# analog.net
KiCad netlist of a schematic drawn in Altium Designer
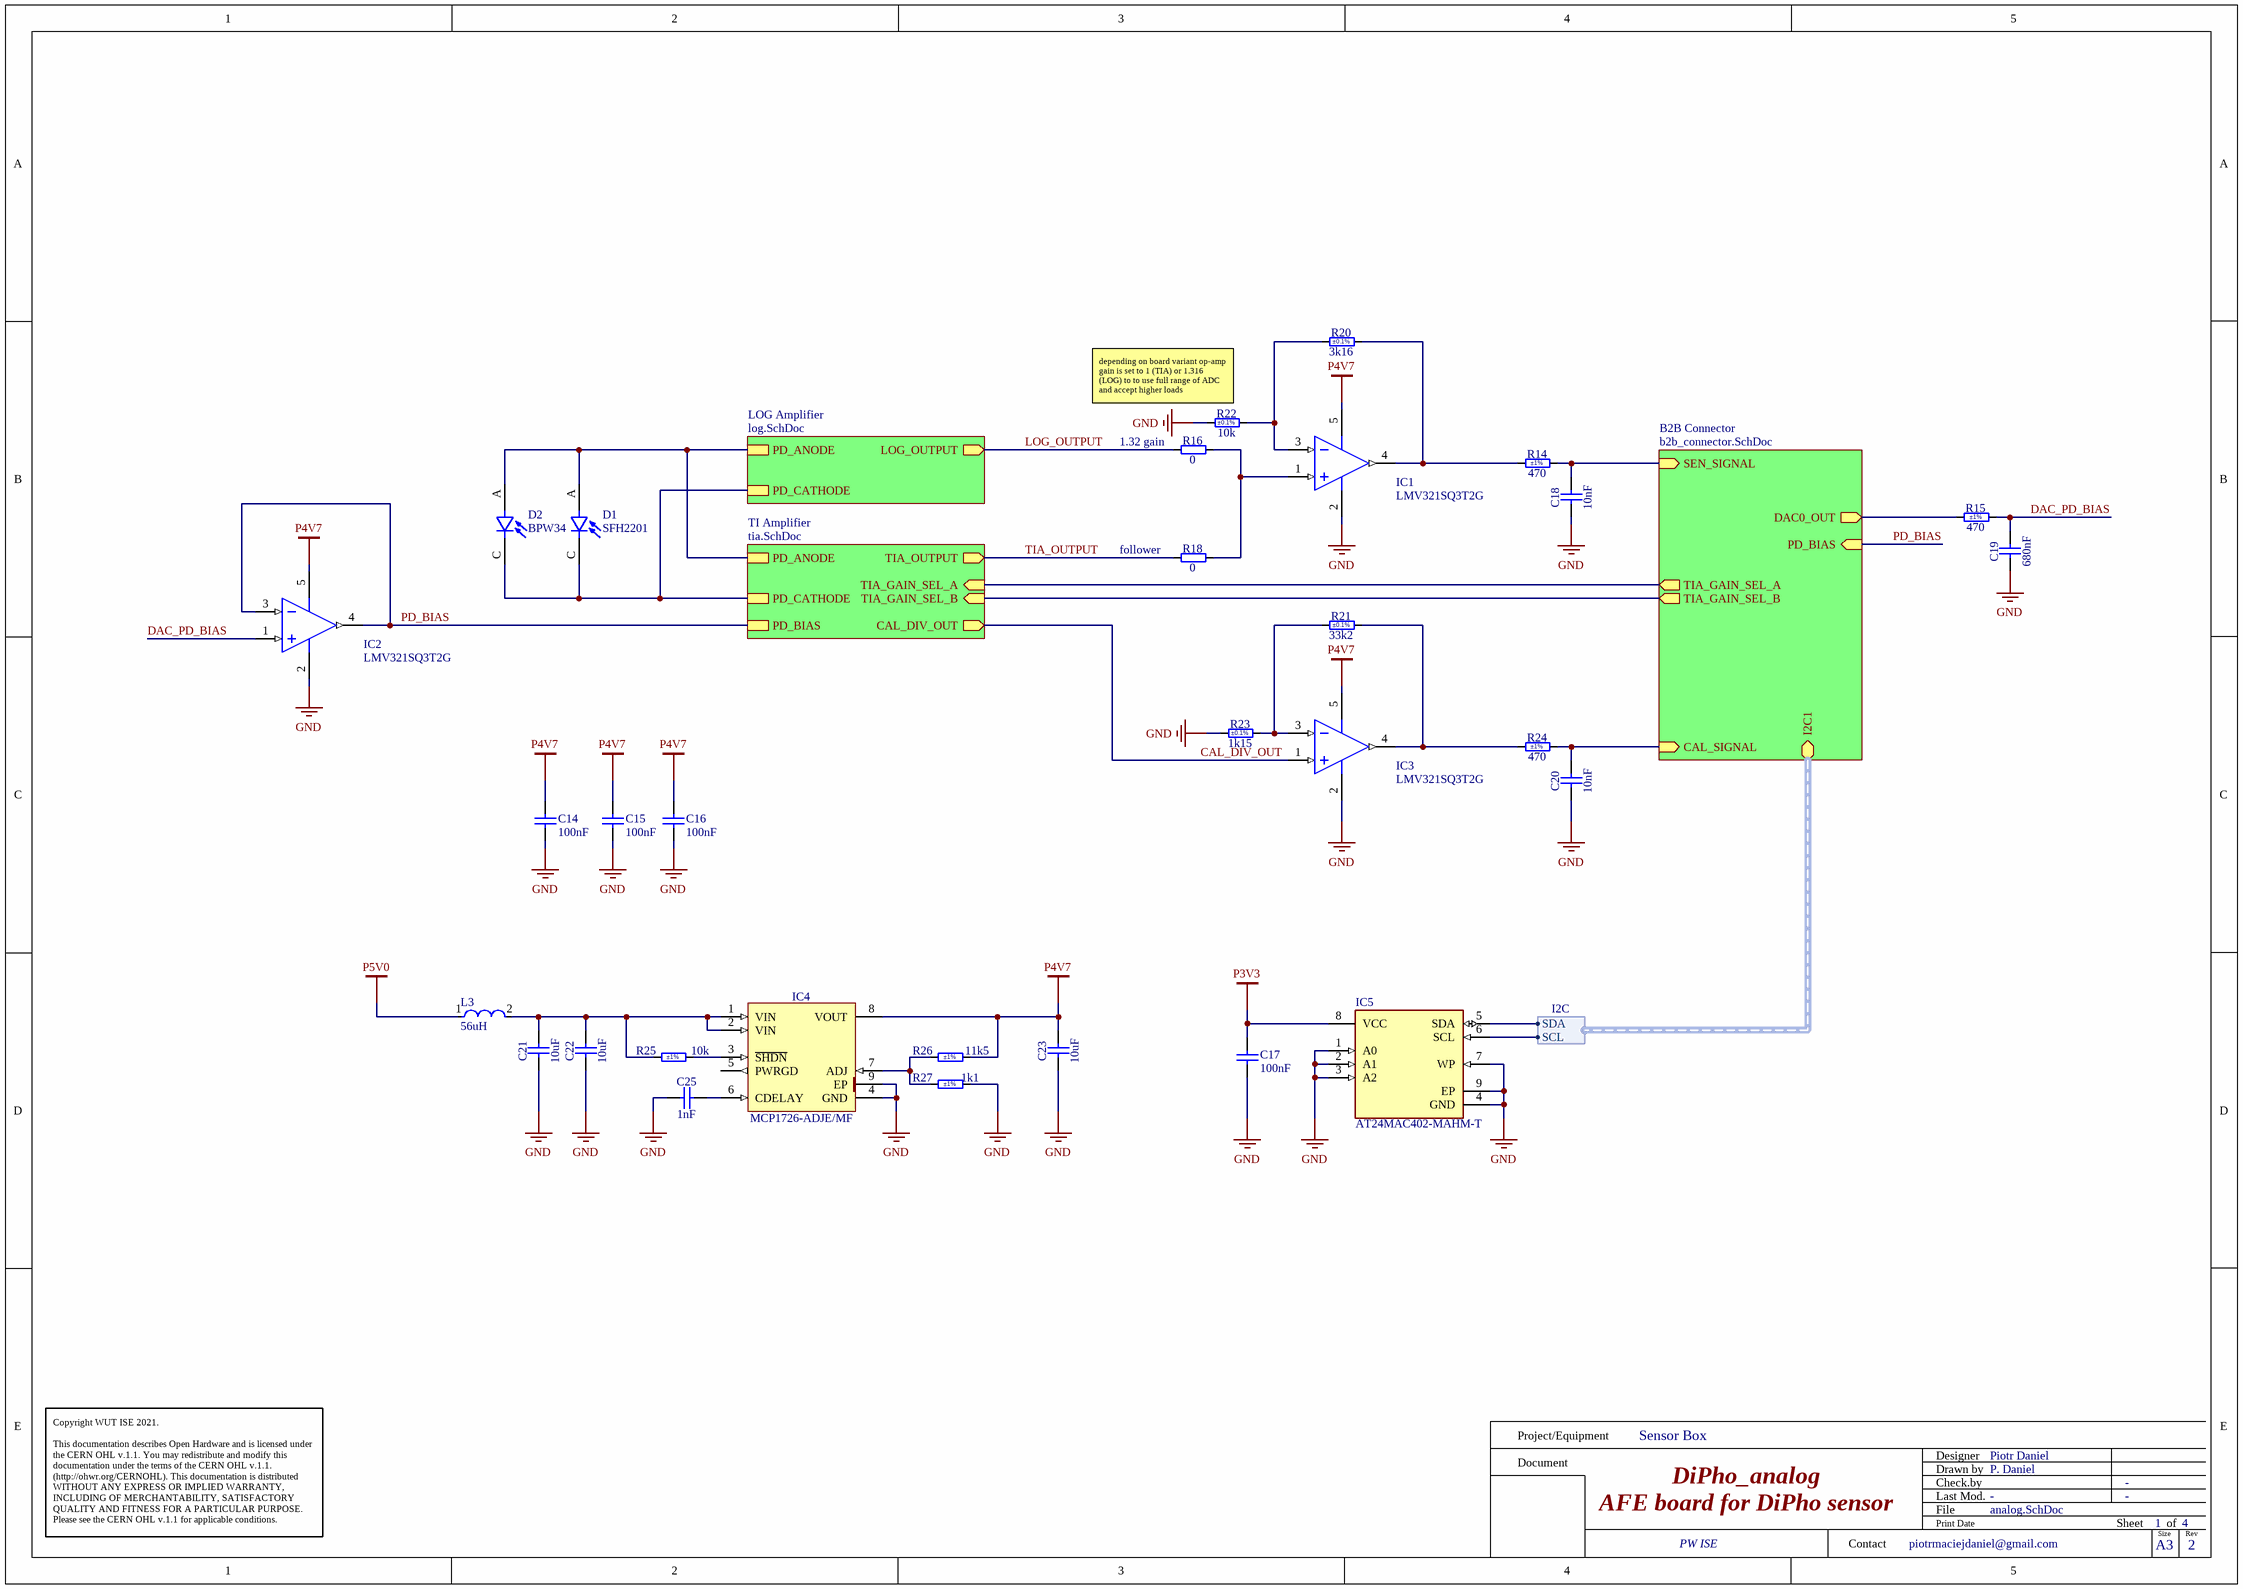
[diagram p0: analog.SchDoc]

(export (version "E")
  (design (tool "Eeschema 10.0.6"))
  (components
    (comp (ref "C14")
      (value "100nF")
      (footprint "CAPC1005X55N")
      (description "Non-polarised capacitor")
      (fields
        (field (name "TOLERANCE") "±10%")
        (field (name "VOLTAGE") "16V")
        (field (name "AUTHOR") "CERN DEM JLC")
      )
      (libsource (lib "Capacitors") (part "Capacitor - non polarized"))
    )
    (comp (ref "C15")
      (value "100nF")
      (footprint "CAPC1005X55N")
      (description "Non-polarised capacitor")
      (fields
        (field (name "TOLERANCE") "±10%")
        (field (name "VOLTAGE") "16V")
        (field (name "AUTHOR") "CERN DEM JLC")
      )
      (libsource (lib "Capacitors") (part "Capacitor - non polarized"))
    )
    (comp (ref "C16")
      (value "100nF")
      (footprint "CAPC1005X55N")
      (description "Non-polarised capacitor")
      (fields
        (field (name "TOLERANCE") "±10%")
        (field (name "VOLTAGE") "16V")
        (field (name "AUTHOR") "CERN DEM JLC")
      )
      (libsource (lib "Capacitors") (part "Capacitor - non polarized"))
    )
    (comp (ref "C17")
      (value "100nF")
      (footprint "CAPC1005X55N")
      (description "Non-polarised capacitor")
      (fields
        (field (name "TOLERANCE") "±10%")
        (field (name "VOLTAGE") "16V")
        (field (name "AUTHOR") "CERN DEM JLC")
      )
      (libsource (lib "Capacitors") (part "Capacitor - non polarized"))
    )
    (comp (ref "C18")
      (value "10nF")
      (footprint "CAPC1005X55N")
      (description "Non-polarised capacitor")
      (fields
        (field (name "PART NUMBER") "CC0402_10NF_16V_10%_X7R")
        (field (name "VOLTAGE") "16V")
        (field (name "AUTHOR") "CERN DEM JLC")
      )
      (libsource (lib "Capacitors") (part "Capacitor - non polarized"))
    )
    (comp (ref "C19")
      (value "680nF")
      (footprint "CAPC1005X55N")
      (description "Non-polarised capacitor")
      (fields
        (field (name "PART NUMBER") "CC0402_680NF_10V_10%_X5R")
        (field (name "VOLTAGE") "10V")
        (field (name "AUTHOR") "CERN DEM BC")
      )
      (libsource (lib "Capacitors") (part "Capacitor - non polarized"))
    )
    (comp (ref "C20")
      (value "10nF")
      (footprint "CAPC1005X55N")
      (description "Non-polarised capacitor")
      (fields
        (field (name "PART NUMBER") "CC0402_10NF_16V_10%_X7R")
        (field (name "VOLTAGE") "16V")
        (field (name "AUTHOR") "CERN DEM JLC")
      )
      (libsource (lib "Capacitors") (part "Capacitor - non polarized"))
    )
    (comp (ref "C21")
      (value "10uF")
      (footprint "CAPC2012X135N")
      (description "Non-polarised capacitor")
      (fields
        (field (name "PART NUMBER") "CC0805_10UF_10V_10%_X7R")
        (field (name "VOLTAGE") "10V")
        (field (name "AUTHOR") "CERN DEM JLC")
      )
      (libsource (lib "Capacitors") (part "Capacitor - non polarized"))
    )
    (comp (ref "C22")
      (value "10uF")
      (footprint "CAPC2012X135N")
      (description "Non-polarised capacitor")
      (fields
        (field (name "PART NUMBER") "CC0805_10UF_10V_10%_X7R")
        (field (name "VOLTAGE") "10V")
        (field (name "AUTHOR") "CERN DEM JLC")
      )
      (libsource (lib "Capacitors") (part "Capacitor - non polarized"))
    )
    (comp (ref "C23")
      (value "10uF")
      (footprint "CAPC2012X135N")
      (description "Non-polarised capacitor")
      (fields
        (field (name "PART NUMBER") "CC0805_10UF_10V_10%_X7R")
        (field (name "VOLTAGE") "10V")
        (field (name "AUTHOR") "CERN DEM JLC")
      )
      (libsource (lib "Capacitors") (part "Capacitor - non polarized"))
    )
    (comp (ref "C25")
      (value "1nF")
      (footprint "CAPC1005X55N")
      (description "Non-polarised capacitor")
      (fields
        (field (name "PART NUMBER") "CC0402_1NF_50V_10%_X7R")
        (field (name "VOLTAGE") "50V")
        (field (name "AUTHOR") "CERN DEM JLC")
      )
      (libsource (lib "Capacitors") (part "Capacitor - non polarized"))
    )
    (comp (ref "D1") (value "SFH2201") (footprint "SFH_2201") (libsource (lib "DiPho") (part "SFH2201")))
    (comp (ref "D2")
      (value "BPW34")
      (footprint "BPW34")
      (description "VISHAY - BPW34 - Photodiode, 65 °, 2 nA, 900 nm, DIP-2")
      (fields (field (name "MANUFACTURER") "Vishay"))
      (libsource (lib "DiPho") (part "BPW34"))
    )
    (comp (ref "IC1")
      (value "LMV321SQ3T2G")
      (footprint "ONSC-SC70-5-419A-02_K_N")
      (fields (field (name "MANUFACTURER") "On Semiconductor"))
      (libsource (lib "Altium Content Vault") (part "ONSC-LMV321-SC70-5-419A-02"))
    )
    (comp (ref "IC2")
      (value "LMV321SQ3T2G")
      (footprint "ONSC-SC70-5-419A-02_K_N")
      (fields (field (name "MANUFACTURER") "On Semiconductor"))
      (libsource (lib "Altium Content Vault") (part "ONSC-LMV321-SC70-5-419A-02"))
    )
    (comp (ref "IC3")
      (value "LMV321SQ3T2G")
      (footprint "ONSC-SC70-5-419A-02_K_N")
      (fields (field (name "MANUFACTURER") "On Semiconductor"))
      (libsource (lib "Altium Content Vault") (part "ONSC-LMV321-SC70-5-419A-02"))
    )
    (comp (ref "IC4")
      (value "MCP1726-ADJE/MF")
      (footprint "SON65P300X300X100-9N-R160X240")
      (description "1A, 0.8V to 5.0V Adjustable , Low Quiescent Current LDO Regulator")
      (fields (field (name "MANUFACTURER") "MICROCHIP TECHNOLOGY") (field (name "AUTHOR") "CERN DEM JLC"))
      (libsource (lib "ICs And Semiconductors") (part "MCP1726-ADJE/MF"))
    )
    (comp (ref "IC5")
      (value "AT24MAC402-MAHM-T")
      (footprint "FP-C04-21355-Q4B-MFG")
      (description "IC EEPROM 2K I2C 1MHZ 8UDFN")
      (libsource (lib "Altium Content Vault") (part "d3f380e7e9881dc7528c8402481fd2f"))
    )
    (comp (ref "L3")
      (value "56uH")
      (footprint "FP-LQH3NPH_ME-MFG")
      (description "Wire Wound Ferrite Inductor for Power Lines 56μH ±20% 1.2Ω 500mA 1212")
      (libsource (lib "Altium Content Vault") (part "725321dda6339637d4d059423bc1c3c"))
    )
    (comp (ref "R14")
      (value "470")
      (footprint "RESC1005X40N")
      (description "Resistor - 1%")
      (fields
        (field (name "TOLERANCE") "±1%")
        (field (name "PART NUMBER") "R0402_470R_1%_0.0625W_100PPM")
        (field (name "POWER") "0.0625W")
        (field (name "AUTHOR") "CERN DEM JLC")
      )
      (libsource (lib "Resistors") (part "Resistor - 1%"))
    )
    (comp (ref "R15")
      (value "470")
      (footprint "RESC1005X40N")
      (description "Resistor - 1%")
      (fields
        (field (name "TOLERANCE") "±1%")
        (field (name "PART NUMBER") "R0402_470R_1%_0.0625W_100PPM")
        (field (name "POWER") "0.0625W")
        (field (name "AUTHOR") "CERN DEM JLC")
      )
      (libsource (lib "Resistors") (part "Resistor - 1%"))
    )
    (comp (ref "R16")
      (value "0")
      (footprint "RESC1005X40N")
      (description "Resistor")
      (fields
        (field (name "PART NUMBER") "R0402_0R_JUMPER")
        (field (name "MANUFACTURER") "GENERIC")
        (field (name "AUTHOR") "CERN DEM JLC")
      )
      (libsource (lib "Resistors") (part "Resistor"))
    )
    (comp (ref "R18")
      (value "0")
      (footprint "RESC1005X40N")
      (description "Resistor")
      (fields
        (field (name "PART NUMBER") "R0402_0R_JUMPER")
        (field (name "MANUFACTURER") "GENERIC")
        (field (name "AUTHOR") "CERN DEM JLC")
      )
      (libsource (lib "Resistors") (part "Resistor"))
    )
    (comp (ref "R20")
      (value "3k16")
      (footprint "RESC1005X35N")
      (description "Resistor - 0.1%")
      (fields
        (field (name "TOLERANCE") "±0.1%")
        (field (name "PART NUMBER") "R0402_10K_0.1%_0.063W_25PPM")
        (field (name "POWER") "0.063W")
        (field (name "AUTHOR") "CERN DEM JMW")
      )
      (libsource (lib "Resistors") (part "Resistor - 0.1%"))
    )
    (comp (ref "R21")
      (value "33k2")
      (footprint "RESC1005X40N")
      (description "Resistor - 0.1%")
      (fields
        (field (name "TOLERANCE") "±0.1%")
        (field (name "PART NUMBER") "R0402_33K2_0.1%_0.063W_25PPM")
        (field (name "POWER") "0.063W")
        (field (name "AUTHOR") "CERN DEM BC")
      )
      (libsource (lib "Resistors") (part "Resistor - 0.1%"))
    )
    (comp (ref "R22")
      (value "10k")
      (footprint "RESC1005X35N")
      (description "Resistor - 0.1%")
      (fields
        (field (name "TOLERANCE") "±0.1%")
        (field (name "PART NUMBER") "R0402_10K_0.1%_0.063W_25PPM")
        (field (name "POWER") "0.063W")
        (field (name "AUTHOR") "CERN DEM JMW")
      )
      (libsource (lib "Resistors") (part "Resistor - 0.1%"))
    )
    (comp (ref "R23")
      (value "1k15")
      (footprint "RESC1005X35N")
      (description "Resistor - 0.1%")
      (fields
        (field (name "TOLERANCE") "±0.1%")
        (field (name "PART NUMBER") "R0402_10K_0.1%_0.063W_25PPM")
        (field (name "POWER") "0.063W")
        (field (name "AUTHOR") "CERN DEM JMW")
      )
      (libsource (lib "Resistors") (part "Resistor - 0.1%"))
    )
    (comp (ref "R24")
      (value "470")
      (footprint "RESC1005X40N")
      (description "Resistor - 1%")
      (fields
        (field (name "TOLERANCE") "±1%")
        (field (name "PART NUMBER") "R0402_470R_1%_0.0625W_100PPM")
        (field (name "POWER") "0.0625W")
        (field (name "AUTHOR") "CERN DEM JLC")
      )
      (libsource (lib "Resistors") (part "Resistor - 1%"))
    )
    (comp (ref "R25")
      (value "10k")
      (footprint "RESC1005X40N")
      (description "Resistor - 1%")
      (fields
        (field (name "TOLERANCE") "±1%")
        (field (name "PART NUMBER") "R0402_10K_1%_0.0625W_100PPM")
        (field (name "POWER") "0.0625W")
        (field (name "AUTHOR") "CERN DEM JLC")
      )
      (libsource (lib "Resistors") (part "Resistor - 1%"))
    )
    (comp (ref "R26")
      (value "11k5")
      (footprint "RESC1005X40N")
      (description "Resistor - 1%")
      (fields
        (field (name "TOLERANCE") "±1%")
        (field (name "PART NUMBER") "R0402_11K5_1%_0.063W_100PPM")
        (field (name "POWER") "0.063W")
        (field (name "AUTHOR") "CERN DEM BC")
      )
      (libsource (lib "Resistors") (part "Resistor - 1%"))
    )
    (comp (ref "R27")
      (value "1k1")
      (footprint "RESC1005X40N")
      (description "Resistor - 1%")
      (fields
        (field (name "TOLERANCE") "±1%")
        (field (name "PART NUMBER") "R0402_1K1_1%_0.0625W_100PPM")
        (field (name "POWER") "0.0625W")
        (field (name "AUTHOR") "CERN DEM JLC")
      )
      (libsource (lib "Resistors") (part "Resistor - 1%"))
    )
  )
  (nets
    (net (code "2") (name "/CAL_DIV_OUT") (class "Default")
      (node (ref "IC3") (pin "1") (pinfunction "IN+_1") (pintype "input"))
    )
    (net (code "3") (name "/CAL_SIGNAL") (class "Default")
      (node (ref "C20") (pin "2") (pinfunction "2_2") (pintype "passive"))
      (node (ref "R24") (pin "2") (pinfunction "2_2") (pintype "passive"))
    )
    (net (code "4") (name "/DAC0_OUT") (class "Default")
      (node (ref "R15") (pin "1") (pinfunction "1_1") (pintype "passive"))
    )
    (net (code "5") (name "/DAC_PD_BIAS") (class "Default")
      (node (ref "C19") (pin "2") (pinfunction "2_2") (pintype "passive"))
      (node (ref "IC2") (pin "1") (pinfunction "IN+_1") (pintype "input"))
      (node (ref "R15") (pin "2") (pinfunction "2_2") (pintype "passive"))
    )
    (net (code "6") (name "/LOG_OUTPUT") (class "Default")
      (node (ref "R16") (pin "1") (pinfunction "1_1") (pintype "passive"))
    )
    (net (code "7") (name "/PD_ANODE") (class "Default")
      (node (ref "D1") (pin "A") (pinfunction "A_A") (pintype "passive"))
      (node (ref "D2") (pin "A") (pinfunction "A_A") (pintype "passive"))
    )
    (net (code "8") (name "/PD_BIAS") (class "Default")
      (node (ref "IC2") (pin "3") (pinfunction "IN-_3") (pintype "input"))
      (node (ref "IC2") (pin "4") (pinfunction "OUT_4") (pintype "output"))
    )
    (net (code "9") (name "/PD_CATHODE") (class "Default")
      (node (ref "D1") (pin "C") (pinfunction "C_C") (pintype "passive"))
      (node (ref "D2") (pin "C") (pinfunction "C_C") (pintype "passive"))
    )
    (net (code "10") (name "/SCL") (class "Default")
      (node (ref "IC5") (pin "6") (pinfunction "SCL_6") (pintype "input"))
    )
    (net (code "11") (name "/SDA") (class "Default")
      (node (ref "IC5") (pin "5") (pinfunction "SDA_5") (pintype "bidirectional"))
    )
    (net (code "12") (name "/SEN_SIGNAL") (class "Default")
      (node (ref "C18") (pin "2") (pinfunction "2_2") (pintype "passive"))
      (node (ref "R14") (pin "2") (pinfunction "2_2") (pintype "passive"))
    )
    (net (code "15") (name "/TIA_OUTPUT") (class "Default")
      (node (ref "R18") (pin "1") (pinfunction "1_1") (pintype "passive"))
    )
    (net (code "17") (name "GND") (class "Default")
      (node (ref "C14") (pin "1") (pinfunction "1_1") (pintype "passive"))
      (node (ref "C15") (pin "1") (pinfunction "1_1") (pintype "passive"))
      (node (ref "C16") (pin "1") (pinfunction "1_1") (pintype "passive"))
      (node (ref "C17") (pin "1") (pinfunction "1_1") (pintype "passive"))
      (node (ref "C18") (pin "1") (pinfunction "1_1") (pintype "passive"))
      (node (ref "C19") (pin "1") (pinfunction "1_1") (pintype "passive"))
      (node (ref "C20") (pin "1") (pinfunction "1_1") (pintype "passive"))
      (node (ref "C21") (pin "1") (pinfunction "1_1") (pintype "passive"))
      (node (ref "C22") (pin "1") (pinfunction "1_1") (pintype "passive"))
      (node (ref "C23") (pin "1") (pinfunction "1_1") (pintype "passive"))
      (node (ref "C25") (pin "1") (pinfunction "1_1") (pintype "passive"))
      (node (ref "IC1") (pin "2") (pinfunction "V-_2") (pintype "power_in"))
      (node (ref "IC2") (pin "2") (pinfunction "V-_2") (pintype "power_in"))
      (node (ref "IC3") (pin "2") (pinfunction "V-_2") (pintype "power_in"))
      (node (ref "IC4") (pin "4") (pinfunction "GND_4") (pintype "power_in"))
      (node (ref "IC4") (pin "9") (pinfunction "EP_9") (pintype "power_in"))
      (node (ref "IC5") (pin "1") (pinfunction "A0_1") (pintype "input"))
      (node (ref "IC5") (pin "2") (pinfunction "A1_2") (pintype "input"))
      (node (ref "IC5") (pin "3") (pinfunction "A2_3") (pintype "input"))
      (node (ref "IC5") (pin "4") (pinfunction "GND_4") (pintype "power_in"))
      (node (ref "IC5") (pin "7") (pinfunction "WP_7") (pintype "input"))
      (node (ref "IC5") (pin "9") (pinfunction "EP_9") (pintype "power_in"))
      (node (ref "R22") (pin "1") (pinfunction "1_1") (pintype "passive"))
      (node (ref "R23") (pin "1") (pinfunction "1_1") (pintype "passive"))
      (node (ref "R27") (pin "2") (pinfunction "2_2") (pintype "passive"))
    )
    (net (code "18") (name "Net-(C21-Pad2)") (class "Default")
      (node (ref "C21") (pin "2") (pinfunction "2_2") (pintype "passive"))
      (node (ref "C22") (pin "2") (pinfunction "2_2") (pintype "passive"))
      (node (ref "IC4") (pin "1") (pinfunction "VIN_1") (pintype "input"))
      (node (ref "IC4") (pin "2") (pinfunction "VIN_2") (pintype "input"))
      (node (ref "L3") (pin "2") (pinfunction "2_2") (pintype "passive"))
      (node (ref "R25") (pin "1") (pinfunction "1_1") (pintype "passive"))
    )
    (net (code "19") (name "Net-(IC1-IN+)") (class "Default")
      (node (ref "IC1") (pin "1") (pinfunction "IN+_1") (pintype "input"))
      (node (ref "R16") (pin "2") (pinfunction "2_2") (pintype "passive"))
      (node (ref "R18") (pin "2") (pinfunction "2_2") (pintype "passive"))
    )
    (net (code "20") (name "Net-(IC1-IN-)") (class "Default")
      (node (ref "IC1") (pin "3") (pinfunction "IN-_3") (pintype "input"))
      (node (ref "R20") (pin "1") (pinfunction "1_1") (pintype "passive"))
      (node (ref "R22") (pin "2") (pinfunction "2_2") (pintype "passive"))
    )
    (net (code "21") (name "Net-(IC1-OUT)") (class "Default")
      (node (ref "IC1") (pin "4") (pinfunction "OUT_4") (pintype "output"))
      (node (ref "R14") (pin "1") (pinfunction "1_1") (pintype "passive"))
      (node (ref "R20") (pin "2") (pinfunction "2_2") (pintype "passive"))
    )
    (net (code "22") (name "Net-(IC3-IN-)") (class "Default")
      (node (ref "IC3") (pin "3") (pinfunction "IN-_3") (pintype "input"))
      (node (ref "R21") (pin "1") (pinfunction "1_1") (pintype "passive"))
      (node (ref "R23") (pin "2") (pinfunction "2_2") (pintype "passive"))
    )
    (net (code "23") (name "Net-(IC3-OUT)") (class "Default")
      (node (ref "IC3") (pin "4") (pinfunction "OUT_4") (pintype "output"))
      (node (ref "R21") (pin "2") (pinfunction "2_2") (pintype "passive"))
      (node (ref "R24") (pin "1") (pinfunction "1_1") (pintype "passive"))
    )
    (net (code "24") (name "Net-(IC4-ADJ)") (class "Default")
      (node (ref "IC4") (pin "7") (pinfunction "ADJ_7") (pintype "input"))
      (node (ref "R26") (pin "1") (pinfunction "1_1") (pintype "passive"))
      (node (ref "R27") (pin "1") (pinfunction "1_1") (pintype "passive"))
    )
    (net (code "25") (name "Net-(IC4-CDELAY)") (class "Default")
      (node (ref "C25") (pin "2") (pinfunction "2_2") (pintype "passive"))
      (node (ref "IC4") (pin "6") (pinfunction "CDELAY_6") (pintype "input"))
    )
    (net (code "26") (name "Net-(IC4-~{SHDN})") (class "Default")
      (node (ref "IC4") (pin "3") (pinfunction "~{SHDN}_3") (pintype "input"))
      (node (ref "R25") (pin "2") (pinfunction "2_2") (pintype "passive"))
    )
    (net (code "27") (name "P3V3") (class "Default")
      (node (ref "C17") (pin "2") (pinfunction "2_2") (pintype "passive"))
      (node (ref "IC5") (pin "8") (pinfunction "VCC_8") (pintype "power_in"))
    )
    (net (code "28") (name "P4V7") (class "Default")
      (node (ref "C14") (pin "2") (pinfunction "2_2") (pintype "passive"))
      (node (ref "C15") (pin "2") (pinfunction "2_2") (pintype "passive"))
      (node (ref "C16") (pin "2") (pinfunction "2_2") (pintype "passive"))
      (node (ref "C23") (pin "2") (pinfunction "2_2") (pintype "passive"))
      (node (ref "IC1") (pin "5") (pinfunction "V+_5") (pintype "power_in"))
      (node (ref "IC2") (pin "5") (pinfunction "V+_5") (pintype "power_in"))
      (node (ref "IC3") (pin "5") (pinfunction "V+_5") (pintype "power_in"))
      (node (ref "IC4") (pin "8") (pinfunction "VOUT_8") (pintype "power_in"))
      (node (ref "R26") (pin "2") (pinfunction "2_2") (pintype "passive"))
    )
    (net (code "29") (name "P5V0") (class "Default")
      (node (ref "L3") (pin "1") (pinfunction "1_1") (pintype "passive"))
    )
    (net (code "30") (name "unconnected-(IC4-PWRGD-Pad5)") (class "Default")
      (node (ref "IC4") (pin "5") (pinfunction "PWRGD_5") (pintype "output"))
    )
  )
)
